# Input_Cover_Flex.net
KiCad netlist of a schematic drawn in Altium Designer
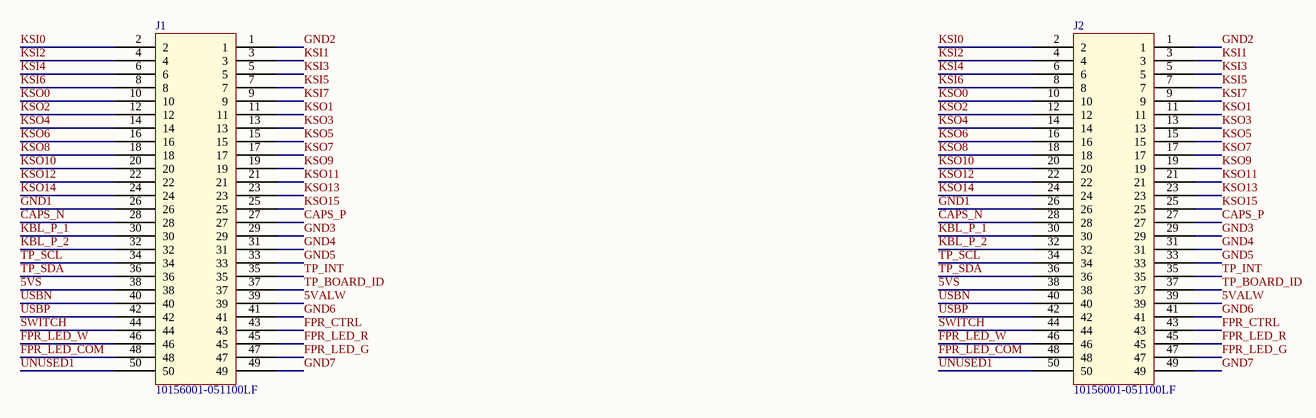
[diagram p0: Input Cover Flex.SchDoc]

(export (version "E")
  (design (tool "Eeschema 10.0.6"))
  (components
    (comp (ref "J1")
      (value "10156001-051100LF")
      (footprint "10156001-051100LF")
      (libsource (lib "KBuchka-IntLib") (part "10156001-051100LF"))
    )
    (comp (ref "J2")
      (value "10156001-051100LF")
      (footprint "10156001-051100LF")
      (libsource (lib "KBuchka-IntLib") (part "10156001-051100LF"))
    )
  )
  (nets
    (net (code "1") (name "/5VALW") (class "Default")
      (node (ref "J1") (pin "39") (pinfunction "39_39") (pintype "passive"))
      (node (ref "J2") (pin "39") (pinfunction "39_39") (pintype "passive"))
    )
    (net (code "2") (name "/5VS") (class "Default")
      (node (ref "J1") (pin "38") (pinfunction "38_38") (pintype "passive"))
      (node (ref "J2") (pin "38") (pinfunction "38_38") (pintype "passive"))
    )
    (net (code "3") (name "/CAPS_N") (class "Default")
      (node (ref "J1") (pin "28") (pinfunction "28_28") (pintype "passive"))
      (node (ref "J2") (pin "28") (pinfunction "28_28") (pintype "passive"))
    )
    (net (code "4") (name "/CAPS_P") (class "Default")
      (node (ref "J1") (pin "27") (pinfunction "27_27") (pintype "passive"))
      (node (ref "J2") (pin "27") (pinfunction "27_27") (pintype "passive"))
    )
    (net (code "5") (name "/FPR_CTRL") (class "Default")
      (node (ref "J1") (pin "43") (pinfunction "43_43") (pintype "passive"))
      (node (ref "J2") (pin "43") (pinfunction "43_43") (pintype "passive"))
    )
    (net (code "6") (name "/FPR_LED_COM") (class "Default")
      (node (ref "J1") (pin "48") (pinfunction "48_48") (pintype "passive"))
      (node (ref "J2") (pin "48") (pinfunction "48_48") (pintype "passive"))
    )
    (net (code "7") (name "/FPR_LED_G") (class "Default")
      (node (ref "J1") (pin "47") (pinfunction "47_47") (pintype "passive"))
      (node (ref "J2") (pin "47") (pinfunction "47_47") (pintype "passive"))
    )
    (net (code "8") (name "/FPR_LED_R") (class "Default")
      (node (ref "J1") (pin "45") (pinfunction "45_45") (pintype "passive"))
      (node (ref "J2") (pin "45") (pinfunction "45_45") (pintype "passive"))
    )
    (net (code "9") (name "/FPR_LED_W") (class "Default")
      (node (ref "J1") (pin "46") (pinfunction "46_46") (pintype "passive"))
      (node (ref "J2") (pin "46") (pinfunction "46_46") (pintype "passive"))
    )
    (net (code "10") (name "/GND1") (class "Default")
      (node (ref "J1") (pin "26") (pinfunction "26_26") (pintype "passive"))
      (node (ref "J2") (pin "26") (pinfunction "26_26") (pintype "passive"))
    )
    (net (code "11") (name "/GND2") (class "Default")
      (node (ref "J1") (pin "1") (pinfunction "1_1") (pintype "passive"))
      (node (ref "J2") (pin "1") (pinfunction "1_1") (pintype "passive"))
    )
    (net (code "12") (name "/GND3") (class "Default")
      (node (ref "J1") (pin "29") (pinfunction "29_29") (pintype "passive"))
      (node (ref "J2") (pin "29") (pinfunction "29_29") (pintype "passive"))
    )
    (net (code "13") (name "/GND4") (class "Default")
      (node (ref "J1") (pin "31") (pinfunction "31_31") (pintype "passive"))
      (node (ref "J2") (pin "31") (pinfunction "31_31") (pintype "passive"))
    )
    (net (code "14") (name "/GND5") (class "Default")
      (node (ref "J1") (pin "33") (pinfunction "33_33") (pintype "passive"))
      (node (ref "J2") (pin "33") (pinfunction "33_33") (pintype "passive"))
    )
    (net (code "15") (name "/GND6") (class "Default")
      (node (ref "J1") (pin "41") (pinfunction "41_41") (pintype "passive"))
      (node (ref "J2") (pin "41") (pinfunction "41_41") (pintype "passive"))
    )
    (net (code "16") (name "/GND7") (class "Default")
      (node (ref "J1") (pin "49") (pinfunction "49_49") (pintype "passive"))
      (node (ref "J2") (pin "49") (pinfunction "49_49") (pintype "passive"))
    )
    (net (code "17") (name "/KBL_P_1") (class "Default")
      (node (ref "J1") (pin "30") (pinfunction "30_30") (pintype "passive"))
      (node (ref "J2") (pin "30") (pinfunction "30_30") (pintype "passive"))
    )
    (net (code "18") (name "/KBL_P_2") (class "Default")
      (node (ref "J1") (pin "32") (pinfunction "32_32") (pintype "passive"))
      (node (ref "J2") (pin "32") (pinfunction "32_32") (pintype "passive"))
    )
    (net (code "19") (name "/KSI0") (class "Default")
      (node (ref "J1") (pin "2") (pinfunction "2_2") (pintype "passive"))
      (node (ref "J2") (pin "2") (pinfunction "2_2") (pintype "passive"))
    )
    (net (code "20") (name "/KSI1") (class "Default")
      (node (ref "J1") (pin "3") (pinfunction "3_3") (pintype "passive"))
      (node (ref "J2") (pin "3") (pinfunction "3_3") (pintype "passive"))
    )
    (net (code "21") (name "/KSI2") (class "Default")
      (node (ref "J1") (pin "4") (pinfunction "4_4") (pintype "passive"))
      (node (ref "J2") (pin "4") (pinfunction "4_4") (pintype "passive"))
    )
    (net (code "22") (name "/KSI3") (class "Default")
      (node (ref "J1") (pin "5") (pinfunction "5_5") (pintype "passive"))
      (node (ref "J2") (pin "5") (pinfunction "5_5") (pintype "passive"))
    )
    (net (code "23") (name "/KSI4") (class "Default")
      (node (ref "J1") (pin "6") (pinfunction "6_6") (pintype "passive"))
      (node (ref "J2") (pin "6") (pinfunction "6_6") (pintype "passive"))
    )
    (net (code "24") (name "/KSI5") (class "Default")
      (node (ref "J1") (pin "7") (pinfunction "7_7") (pintype "passive"))
      (node (ref "J2") (pin "7") (pinfunction "7_7") (pintype "passive"))
    )
    (net (code "25") (name "/KSI6") (class "Default")
      (node (ref "J1") (pin "8") (pinfunction "8_8") (pintype "passive"))
      (node (ref "J2") (pin "8") (pinfunction "8_8") (pintype "passive"))
    )
    (net (code "26") (name "/KSI7") (class "Default")
      (node (ref "J1") (pin "9") (pinfunction "9_9") (pintype "passive"))
      (node (ref "J2") (pin "9") (pinfunction "9_9") (pintype "passive"))
    )
    (net (code "27") (name "/KSO0") (class "Default")
      (node (ref "J1") (pin "10") (pinfunction "10_10") (pintype "passive"))
      (node (ref "J2") (pin "10") (pinfunction "10_10") (pintype "passive"))
    )
    (net (code "28") (name "/KSO1") (class "Default")
      (node (ref "J1") (pin "11") (pinfunction "11_11") (pintype "passive"))
      (node (ref "J2") (pin "11") (pinfunction "11_11") (pintype "passive"))
    )
    (net (code "29") (name "/KSO2") (class "Default")
      (node (ref "J1") (pin "12") (pinfunction "12_12") (pintype "passive"))
      (node (ref "J2") (pin "12") (pinfunction "12_12") (pintype "passive"))
    )
    (net (code "30") (name "/KSO3") (class "Default")
      (node (ref "J1") (pin "13") (pinfunction "13_13") (pintype "passive"))
      (node (ref "J2") (pin "13") (pinfunction "13_13") (pintype "passive"))
    )
    (net (code "31") (name "/KSO4") (class "Default")
      (node (ref "J1") (pin "14") (pinfunction "14_14") (pintype "passive"))
      (node (ref "J2") (pin "14") (pinfunction "14_14") (pintype "passive"))
    )
    (net (code "32") (name "/KSO5") (class "Default")
      (node (ref "J1") (pin "15") (pinfunction "15_15") (pintype "passive"))
      (node (ref "J2") (pin "15") (pinfunction "15_15") (pintype "passive"))
    )
    (net (code "33") (name "/KSO6") (class "Default")
      (node (ref "J1") (pin "16") (pinfunction "16_16") (pintype "passive"))
      (node (ref "J2") (pin "16") (pinfunction "16_16") (pintype "passive"))
    )
    (net (code "34") (name "/KSO7") (class "Default")
      (node (ref "J1") (pin "17") (pinfunction "17_17") (pintype "passive"))
      (node (ref "J2") (pin "17") (pinfunction "17_17") (pintype "passive"))
    )
    (net (code "35") (name "/KSO8") (class "Default")
      (node (ref "J1") (pin "18") (pinfunction "18_18") (pintype "passive"))
      (node (ref "J2") (pin "18") (pinfunction "18_18") (pintype "passive"))
    )
    (net (code "36") (name "/KSO9") (class "Default")
      (node (ref "J1") (pin "19") (pinfunction "19_19") (pintype "passive"))
      (node (ref "J2") (pin "19") (pinfunction "19_19") (pintype "passive"))
    )
    (net (code "37") (name "/KSO10") (class "Default")
      (node (ref "J1") (pin "20") (pinfunction "20_20") (pintype "passive"))
      (node (ref "J2") (pin "20") (pinfunction "20_20") (pintype "passive"))
    )
    (net (code "38") (name "/KSO11") (class "Default")
      (node (ref "J1") (pin "21") (pinfunction "21_21") (pintype "passive"))
      (node (ref "J2") (pin "21") (pinfunction "21_21") (pintype "passive"))
    )
    (net (code "39") (name "/KSO12") (class "Default")
      (node (ref "J1") (pin "22") (pinfunction "22_22") (pintype "passive"))
      (node (ref "J2") (pin "22") (pinfunction "22_22") (pintype "passive"))
    )
    (net (code "40") (name "/KSO13") (class "Default")
      (node (ref "J1") (pin "23") (pinfunction "23_23") (pintype "passive"))
      (node (ref "J2") (pin "23") (pinfunction "23_23") (pintype "passive"))
    )
    (net (code "41") (name "/KSO14") (class "Default")
      (node (ref "J1") (pin "24") (pinfunction "24_24") (pintype "passive"))
      (node (ref "J2") (pin "24") (pinfunction "24_24") (pintype "passive"))
    )
    (net (code "42") (name "/KSO15") (class "Default")
      (node (ref "J1") (pin "25") (pinfunction "25_25") (pintype "passive"))
      (node (ref "J2") (pin "25") (pinfunction "25_25") (pintype "passive"))
    )
    (net (code "43") (name "/SWITCH") (class "Default")
      (node (ref "J1") (pin "44") (pinfunction "44_44") (pintype "passive"))
      (node (ref "J2") (pin "44") (pinfunction "44_44") (pintype "passive"))
    )
    (net (code "44") (name "/TP_BOARD_ID") (class "Default")
      (node (ref "J1") (pin "37") (pinfunction "37_37") (pintype "passive"))
      (node (ref "J2") (pin "37") (pinfunction "37_37") (pintype "passive"))
    )
    (net (code "45") (name "/TP_INT") (class "Default")
      (node (ref "J1") (pin "35") (pinfunction "35_35") (pintype "passive"))
      (node (ref "J2") (pin "35") (pinfunction "35_35") (pintype "passive"))
    )
    (net (code "46") (name "/TP_SCL") (class "Default")
      (node (ref "J1") (pin "34") (pinfunction "34_34") (pintype "passive"))
      (node (ref "J2") (pin "34") (pinfunction "34_34") (pintype "passive"))
    )
    (net (code "47") (name "/TP_SDA") (class "Default")
      (node (ref "J1") (pin "36") (pinfunction "36_36") (pintype "passive"))
      (node (ref "J2") (pin "36") (pinfunction "36_36") (pintype "passive"))
    )
    (net (code "48") (name "/UNUSED1") (class "Default")
      (node (ref "J1") (pin "50") (pinfunction "50_50") (pintype "passive"))
      (node (ref "J2") (pin "50") (pinfunction "50_50") (pintype "passive"))
    )
    (net (code "49") (name "/USBN") (class "Default")
      (node (ref "J1") (pin "40") (pinfunction "40_40") (pintype "passive"))
      (node (ref "J2") (pin "40") (pinfunction "40_40") (pintype "passive"))
    )
    (net (code "50") (name "/USBP") (class "Default")
      (node (ref "J1") (pin "42") (pinfunction "42_42") (pintype "passive"))
      (node (ref "J2") (pin "42") (pinfunction "42_42") (pintype "passive"))
    )
  )
)
